# 02-ui.net
KiCad netlist of a schematic drawn in EAGLE
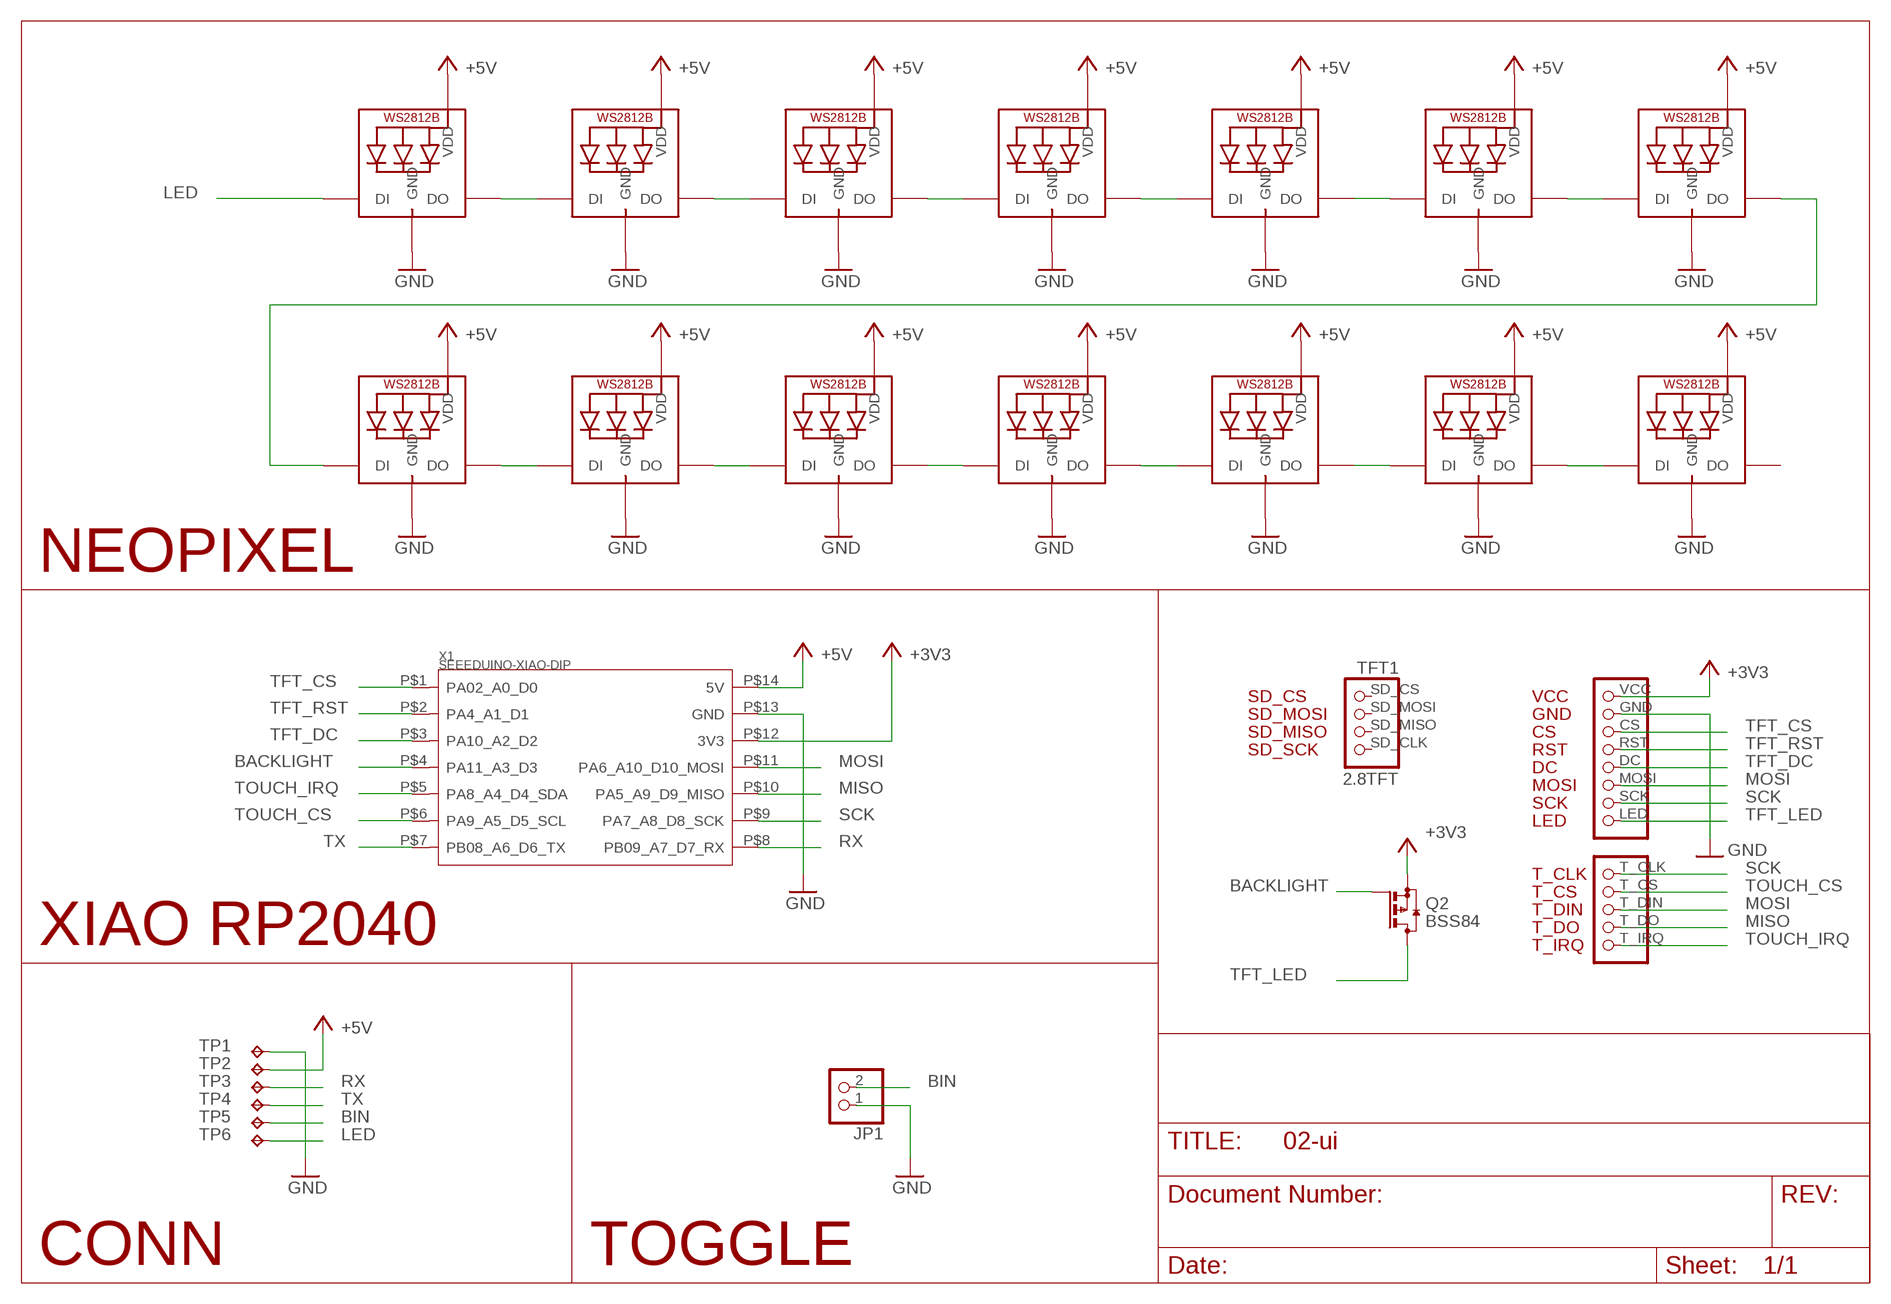
[diagram p0: schematic, sheet 1]

(export (version "E")
  (design (tool "Eeschema 10.0.6"))
  (components
    (comp (ref "JP1")
      (value "PINHD-1X2")
      (footprint "eagle-import:1X02")
      (libsource (lib "eagle-import") (part "PINHD-1X2"))
    )
    (comp (ref "LED1")
      (value "WS2812B_2020")
      (footprint "eagle-import:WS2812B_2020")
      (libsource (lib "eagle-import") (part "WS2812B_2020"))
    )
    (comp (ref "LED2")
      (value "WS2812B_2020")
      (footprint "eagle-import:WS2812B_2020")
      (libsource (lib "eagle-import") (part "WS2812B_2020"))
    )
    (comp (ref "LED3")
      (value "WS2812B_2020")
      (footprint "eagle-import:WS2812B_2020")
      (libsource (lib "eagle-import") (part "WS2812B_2020"))
    )
    (comp (ref "LED4")
      (value "WS2812B_2020")
      (footprint "eagle-import:WS2812B_2020")
      (libsource (lib "eagle-import") (part "WS2812B_2020"))
    )
    (comp (ref "LED5")
      (value "WS2812B_2020")
      (footprint "eagle-import:WS2812B_2020")
      (libsource (lib "eagle-import") (part "WS2812B_2020"))
    )
    (comp (ref "LED6")
      (value "WS2812B_2020")
      (footprint "eagle-import:WS2812B_2020")
      (libsource (lib "eagle-import") (part "WS2812B_2020"))
    )
    (comp (ref "LED7")
      (value "WS2812B_2020")
      (footprint "eagle-import:WS2812B_2020")
      (libsource (lib "eagle-import") (part "WS2812B_2020"))
    )
    (comp (ref "LED8")
      (value "WS2812B_2020")
      (footprint "eagle-import:WS2812B_2020")
      (libsource (lib "eagle-import") (part "WS2812B_2020"))
    )
    (comp (ref "LED9")
      (value "WS2812B_2020")
      (footprint "eagle-import:WS2812B_2020")
      (libsource (lib "eagle-import") (part "WS2812B_2020"))
    )
    (comp (ref "LED10")
      (value "WS2812B_2020")
      (footprint "eagle-import:WS2812B_2020")
      (libsource (lib "eagle-import") (part "WS2812B_2020"))
    )
    (comp (ref "LED11")
      (value "WS2812B_2020")
      (footprint "eagle-import:WS2812B_2020")
      (libsource (lib "eagle-import") (part "WS2812B_2020"))
    )
    (comp (ref "LED12")
      (value "WS2812B_2020")
      (footprint "eagle-import:WS2812B_2020")
      (libsource (lib "eagle-import") (part "WS2812B_2020"))
    )
    (comp (ref "LED13")
      (value "WS2812B_2020")
      (footprint "eagle-import:WS2812B_2020")
      (libsource (lib "eagle-import") (part "WS2812B_2020"))
    )
    (comp (ref "LED14")
      (value "WS2812B_2020")
      (footprint "eagle-import:WS2812B_2020")
      (libsource (lib "eagle-import") (part "WS2812B_2020"))
    )
    (comp (ref "Q2")
      (value "BSS84")
      (footprint "eagle-import:SOT23")
      (libsource (lib "eagle-import") (part "BSS84"))
    )
    (comp (ref "TFT1")
      (value "2.8TFT")
      (footprint "eagle-import:2.8TFT")
      (libsource (lib "eagle-import") (part "2.8TFT"))
    )
    (comp (ref "TP1")
      (value "TPTP10SQ")
      (footprint "eagle-import:TP10SQ")
      (libsource (lib "eagle-import") (part "TPTP10SQ"))
    )
    (comp (ref "TP2")
      (value "TPTP10R")
      (footprint "eagle-import:TP10R")
      (libsource (lib "eagle-import") (part "TPTP10R"))
    )
    (comp (ref "TP3")
      (value "TPTP10R")
      (footprint "eagle-import:TP10R")
      (libsource (lib "eagle-import") (part "TPTP10R"))
    )
    (comp (ref "TP4")
      (value "TPTP10R")
      (footprint "eagle-import:TP10R")
      (libsource (lib "eagle-import") (part "TPTP10R"))
    )
    (comp (ref "TP5")
      (value "TPTP10R")
      (footprint "eagle-import:TP10R")
      (libsource (lib "eagle-import") (part "TPTP10R"))
    )
    (comp (ref "TP6")
      (value "TPTP10R")
      (footprint "eagle-import:TP10R")
      (libsource (lib "eagle-import") (part "TPTP10R"))
    )
    (comp (ref "X1")
      (value "SEEEDUINO-XIAO-DIP")
      (footprint "eagle-import:XIAO-PINHEAD")
      (libsource (lib "eagle-import") (part "SEEEDUINO-XIAO-DIP"))
    )
  )
  (nets
    (net (code "1") (name "+3V3") (class "Default")
      (node (ref "Q2") (pin "2") (pinfunction "S_2") (pintype "passive"))
      (node (ref "TFT1") (pin "VCC") (pinfunction "VCC_VCC") (pintype "passive"))
      (node (ref "X1") (pin "P$12") (pinfunction "3V3_P$12") (pintype "bidirectional"))
    )
    (net (code "2") (name "+5V") (class "Default")
      (node (ref "LED1") (pin "4") (pinfunction "VDD_4") (pintype "power_in"))
      (node (ref "LED10") (pin "4") (pinfunction "VDD_4") (pintype "power_in"))
      (node (ref "LED11") (pin "4") (pinfunction "VDD_4") (pintype "power_in"))
      (node (ref "LED12") (pin "4") (pinfunction "VDD_4") (pintype "power_in"))
      (node (ref "LED13") (pin "4") (pinfunction "VDD_4") (pintype "power_in"))
      (node (ref "LED14") (pin "4") (pinfunction "VDD_4") (pintype "power_in"))
      (node (ref "LED2") (pin "4") (pinfunction "VDD_4") (pintype "power_in"))
      (node (ref "LED3") (pin "4") (pinfunction "VDD_4") (pintype "power_in"))
      (node (ref "LED4") (pin "4") (pinfunction "VDD_4") (pintype "power_in"))
      (node (ref "LED5") (pin "4") (pinfunction "VDD_4") (pintype "power_in"))
      (node (ref "LED6") (pin "4") (pinfunction "VDD_4") (pintype "power_in"))
      (node (ref "LED7") (pin "4") (pinfunction "VDD_4") (pintype "power_in"))
      (node (ref "LED8") (pin "4") (pinfunction "VDD_4") (pintype "power_in"))
      (node (ref "LED9") (pin "4") (pinfunction "VDD_4") (pintype "power_in"))
      (node (ref "TP2") (pin "TP") (pinfunction "TP_TP") (pintype "input"))
      (node (ref "X1") (pin "P$14") (pinfunction "5V_P$14") (pintype "bidirectional"))
    )
    (net (code "3") (name "/BACKLIGHT") (class "Default")
      (node (ref "Q2") (pin "1") (pinfunction "G_1") (pintype "passive"))
      (node (ref "X1") (pin "P$4") (pinfunction "PA11_A3_D3_P$4") (pintype "bidirectional"))
    )
    (net (code "4") (name "/BIN") (class "Default")
      (node (ref "JP1") (pin "2") (pinfunction "2_2") (pintype "passive"))
      (node (ref "TP5") (pin "TP") (pinfunction "TP_TP") (pintype "input"))
    )
    (net (code "5") (name "/LED") (class "Default")
      (node (ref "LED1") (pin "3") (pinfunction "DI_3") (pintype "input"))
      (node (ref "TP6") (pin "TP") (pinfunction "TP_TP") (pintype "input"))
    )
    (net (code "6") (name "/MISO") (class "Default")
      (node (ref "TFT1") (pin "T_DO") (pinfunction "T_DO_T_DO") (pintype "passive"))
      (node (ref "X1") (pin "P$10") (pinfunction "PA5_A9_D9_MISO_P$10") (pintype "bidirectional"))
    )
    (net (code "7") (name "/MOSI") (class "Default")
      (node (ref "TFT1") (pin "MOSI") (pinfunction "MOSI_MOSI") (pintype "passive"))
      (node (ref "TFT1") (pin "T_DIN") (pinfunction "T_DIN_T_DIN") (pintype "passive"))
      (node (ref "X1") (pin "P$11") (pinfunction "PA6_A10_D10_MOSI_P$11") (pintype "bidirectional"))
    )
    (net (code "8") (name "/RX") (class "Default")
      (node (ref "TP3") (pin "TP") (pinfunction "TP_TP") (pintype "input"))
      (node (ref "X1") (pin "P$8") (pinfunction "PB09_A7_D7_RX_P$8") (pintype "bidirectional"))
    )
    (net (code "9") (name "/SCK") (class "Default")
      (node (ref "TFT1") (pin "SCK") (pinfunction "SCK_SCK") (pintype "passive"))
      (node (ref "TFT1") (pin "T_CLK") (pinfunction "T_CLK_T_CLK") (pintype "passive"))
      (node (ref "X1") (pin "P$9") (pinfunction "PA7_A8_D8_SCK_P$9") (pintype "bidirectional"))
    )
    (net (code "10") (name "/TFT_CS") (class "Default")
      (node (ref "TFT1") (pin "CS") (pinfunction "CS_CS") (pintype "passive"))
      (node (ref "X1") (pin "P$1") (pinfunction "PA02_A0_D0_P$1") (pintype "bidirectional"))
    )
    (net (code "11") (name "/TFT_DC") (class "Default")
      (node (ref "TFT1") (pin "DC") (pinfunction "DC_DC") (pintype "passive"))
      (node (ref "X1") (pin "P$3") (pinfunction "PA10_A2_D2_P$3") (pintype "bidirectional"))
    )
    (net (code "12") (name "/TFT_LED") (class "Default")
      (node (ref "Q2") (pin "3") (pinfunction "D_3") (pintype "passive"))
      (node (ref "TFT1") (pin "LED") (pinfunction "LED_LED") (pintype "passive"))
    )
    (net (code "13") (name "/TFT_RST") (class "Default")
      (node (ref "TFT1") (pin "RST") (pinfunction "RST_RST") (pintype "passive"))
      (node (ref "X1") (pin "P$2") (pinfunction "PA4_A1_D1_P$2") (pintype "bidirectional"))
    )
    (net (code "14") (name "/TOUCH_CS") (class "Default")
      (node (ref "TFT1") (pin "T_CS") (pinfunction "T_CS_T_CS") (pintype "passive"))
      (node (ref "X1") (pin "P$6") (pinfunction "PA9_A5_D5_SCL_P$6") (pintype "bidirectional"))
    )
    (net (code "15") (name "/TOUCH_IRQ") (class "Default")
      (node (ref "TFT1") (pin "T_IRQ") (pinfunction "T_IRQ_T_IRQ") (pintype "passive"))
      (node (ref "X1") (pin "P$5") (pinfunction "PA8_A4_D4_SDA_P$5") (pintype "bidirectional"))
    )
    (net (code "16") (name "/TX") (class "Default")
      (node (ref "TP4") (pin "TP") (pinfunction "TP_TP") (pintype "input"))
      (node (ref "X1") (pin "P$7") (pinfunction "PB08_A6_D6_TX_P$7") (pintype "bidirectional"))
    )
    (net (code "17") (name "GND") (class "Default")
      (node (ref "JP1") (pin "1") (pinfunction "1_1") (pintype "passive"))
      (node (ref "LED1") (pin "2") (pinfunction "GND_2") (pintype "power_in"))
      (node (ref "LED10") (pin "2") (pinfunction "GND_2") (pintype "power_in"))
      (node (ref "LED11") (pin "2") (pinfunction "GND_2") (pintype "power_in"))
      (node (ref "LED12") (pin "2") (pinfunction "GND_2") (pintype "power_in"))
      (node (ref "LED13") (pin "2") (pinfunction "GND_2") (pintype "power_in"))
      (node (ref "LED14") (pin "2") (pinfunction "GND_2") (pintype "power_in"))
      (node (ref "LED2") (pin "2") (pinfunction "GND_2") (pintype "power_in"))
      (node (ref "LED3") (pin "2") (pinfunction "GND_2") (pintype "power_in"))
      (node (ref "LED4") (pin "2") (pinfunction "GND_2") (pintype "power_in"))
      (node (ref "LED5") (pin "2") (pinfunction "GND_2") (pintype "power_in"))
      (node (ref "LED6") (pin "2") (pinfunction "GND_2") (pintype "power_in"))
      (node (ref "LED7") (pin "2") (pinfunction "GND_2") (pintype "power_in"))
      (node (ref "LED8") (pin "2") (pinfunction "GND_2") (pintype "power_in"))
      (node (ref "LED9") (pin "2") (pinfunction "GND_2") (pintype "power_in"))
      (node (ref "TFT1") (pin "GND") (pinfunction "GND_GND") (pintype "passive"))
      (node (ref "TP1") (pin "TP") (pinfunction "TP_TP") (pintype "input"))
      (node (ref "X1") (pin "P$13") (pinfunction "GND_P$13") (pintype "bidirectional"))
    )
    (net (code "18") (name "Net-(LED1-DO)") (class "Default")
      (node (ref "LED1") (pin "1") (pinfunction "DO_1") (pintype "output"))
      (node (ref "LED2") (pin "3") (pinfunction "DI_3") (pintype "input"))
    )
    (net (code "19") (name "Net-(LED2-DO)") (class "Default")
      (node (ref "LED2") (pin "1") (pinfunction "DO_1") (pintype "output"))
      (node (ref "LED3") (pin "3") (pinfunction "DI_3") (pintype "input"))
    )
    (net (code "20") (name "Net-(LED3-DO)") (class "Default")
      (node (ref "LED3") (pin "1") (pinfunction "DO_1") (pintype "output"))
      (node (ref "LED4") (pin "3") (pinfunction "DI_3") (pintype "input"))
    )
    (net (code "21") (name "Net-(LED4-DO)") (class "Default")
      (node (ref "LED4") (pin "1") (pinfunction "DO_1") (pintype "output"))
      (node (ref "LED5") (pin "3") (pinfunction "DI_3") (pintype "input"))
    )
    (net (code "22") (name "Net-(LED5-DO)") (class "Default")
      (node (ref "LED5") (pin "1") (pinfunction "DO_1") (pintype "output"))
      (node (ref "LED6") (pin "3") (pinfunction "DI_3") (pintype "input"))
    )
    (net (code "23") (name "Net-(LED6-DO)") (class "Default")
      (node (ref "LED6") (pin "1") (pinfunction "DO_1") (pintype "output"))
      (node (ref "LED7") (pin "3") (pinfunction "DI_3") (pintype "input"))
    )
    (net (code "24") (name "Net-(LED7-DO)") (class "Default")
      (node (ref "LED7") (pin "1") (pinfunction "DO_1") (pintype "output"))
      (node (ref "LED8") (pin "3") (pinfunction "DI_3") (pintype "input"))
    )
    (net (code "25") (name "Net-(LED8-DO)") (class "Default")
      (node (ref "LED8") (pin "1") (pinfunction "DO_1") (pintype "output"))
      (node (ref "LED9") (pin "3") (pinfunction "DI_3") (pintype "input"))
    )
    (net (code "26") (name "Net-(LED10-DI)") (class "Default")
      (node (ref "LED10") (pin "3") (pinfunction "DI_3") (pintype "input"))
      (node (ref "LED9") (pin "1") (pinfunction "DO_1") (pintype "output"))
    )
    (net (code "27") (name "Net-(LED10-DO)") (class "Default")
      (node (ref "LED10") (pin "1") (pinfunction "DO_1") (pintype "output"))
      (node (ref "LED11") (pin "3") (pinfunction "DI_3") (pintype "input"))
    )
    (net (code "28") (name "Net-(LED11-DO)") (class "Default")
      (node (ref "LED11") (pin "1") (pinfunction "DO_1") (pintype "output"))
      (node (ref "LED12") (pin "3") (pinfunction "DI_3") (pintype "input"))
    )
    (net (code "29") (name "Net-(LED12-DO)") (class "Default")
      (node (ref "LED12") (pin "1") (pinfunction "DO_1") (pintype "output"))
      (node (ref "LED13") (pin "3") (pinfunction "DI_3") (pintype "input"))
    )
    (net (code "30") (name "Net-(LED13-DO)") (class "Default")
      (node (ref "LED13") (pin "1") (pinfunction "DO_1") (pintype "output"))
      (node (ref "LED14") (pin "3") (pinfunction "DI_3") (pintype "input"))
    )
    (net (code "31") (name "unconnected-(LED14-DO-Pad1)") (class "Default")
      (node (ref "LED14") (pin "1") (pinfunction "DO_1") (pintype "output"))
    )
    (net (code "32") (name "unconnected-(TFT1-PadSD_CS)") (class "Default")
      (node (ref "TFT1") (pin "SD_CS") (pinfunction "SD_CS_SD_CS") (pintype "passive"))
    )
    (net (code "33") (name "unconnected-(TFT1-PadSD_MISO)") (class "Default")
      (node (ref "TFT1") (pin "SD_MISO") (pinfunction "SD_MISO_SD_MISO") (pintype "passive"))
    )
    (net (code "34") (name "unconnected-(TFT1-PadSD_MOSI)") (class "Default")
      (node (ref "TFT1") (pin "SD_MOSI") (pinfunction "SD_MOSI_SD_MOSI") (pintype "passive"))
    )
    (net (code "35") (name "unconnected-(TFT1-SD_SCK-PadSD_CLK)") (class "Default")
      (node (ref "TFT1") (pin "SD_CLK") (pinfunction "SD_SCK_SD_CLK") (pintype "passive"))
    )
  )
)
